# LeftSide.net
KiCad netlist of a schematic drawn in Altium Designer
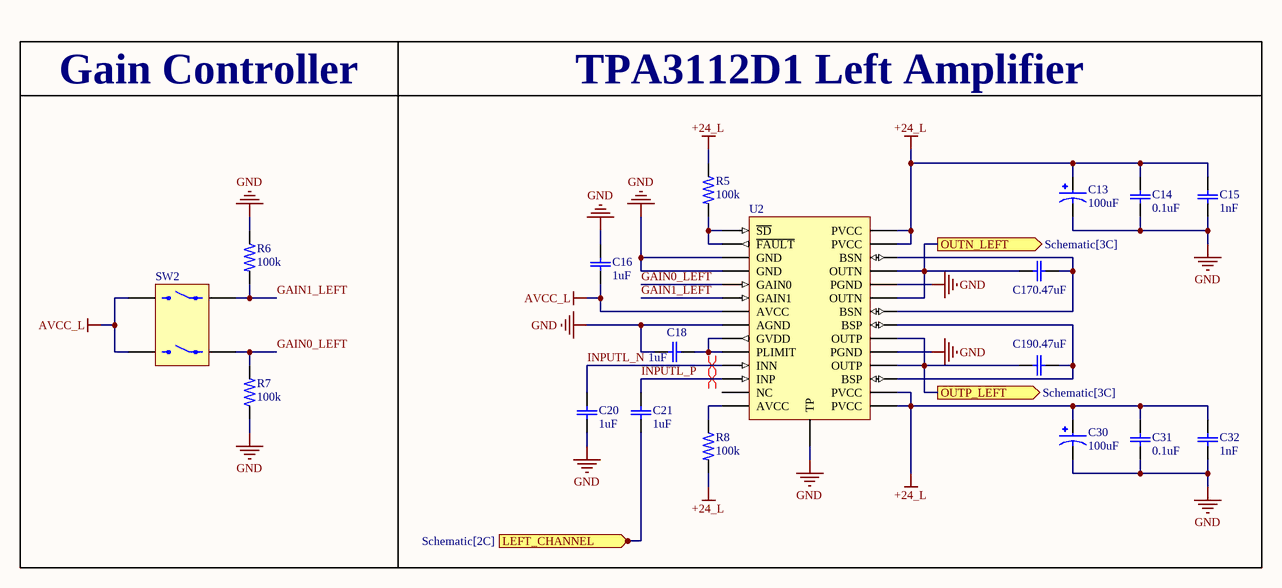
[diagram p0: LeftSide.SchDoc]

(export (version "E")
  (design (tool "Eeschema 10.0.6"))
  (components
    (comp (ref "C13")
      (value "100uF")
      (footprint "CAPRADIAL_16X10")
      (fields
        (field (name "DIGI-KEY_PART_NUMBER") "P13679-ND")
        (field (name "MP") "EEU-EE2W560")
        (field (name "MF") "Panasonic")
      )
      (libsource (lib "AltiumLibrary-Mugetsu") (part "CAP ELETRO/TANT"))
    )
    (comp (ref "C14")
      (value "0.1uF")
      (footprint "CERAMIC0805")
      (fields (field (name "MF") "KEMET") (field (name "MP") "TAJC226M025RNJ"))
      (libsource (lib "AltiumLibrary-Mugetsu") (part "Cap"))
    )
    (comp (ref "C15")
      (value "1nF")
      (footprint "CERAMIC0603")
      (fields (field (name "MF") "KEMET") (field (name "MP") "TAJC226M025RNJ"))
      (libsource (lib "AltiumLibrary-Mugetsu") (part "Cap"))
    )
    (comp (ref "C16")
      (value "1uF")
      (footprint "CERAMIC0603")
      (fields (field (name "MF") "KEMET") (field (name "MP") "TAJC226M025RNJ"))
      (libsource (lib "AltiumLibrary-Mugetsu") (part "Cap"))
    )
    (comp (ref "C17")
      (value "0.47uF")
      (footprint "CERAMIC0603")
      (fields (field (name "MF") "KEMET") (field (name "MP") "TAJC226M025RNJ"))
      (libsource (lib "AltiumLibrary-Mugetsu") (part "Cap"))
    )
    (comp (ref "C18")
      (value "1uF")
      (footprint "CERAMIC0603")
      (fields (field (name "MF") "KEMET") (field (name "MP") "TAJC226M025RNJ"))
      (libsource (lib "AltiumLibrary-Mugetsu") (part "Cap"))
    )
    (comp (ref "C19")
      (value "0.47uF")
      (footprint "CERAMIC0603")
      (fields (field (name "MF") "KEMET") (field (name "MP") "TAJC226M025RNJ"))
      (libsource (lib "AltiumLibrary-Mugetsu") (part "Cap"))
    )
    (comp (ref "C20")
      (value "1uF")
      (footprint "CERAMIC0603")
      (fields (field (name "MF") "KEMET") (field (name "MP") "TAJC226M025RNJ"))
      (libsource (lib "AltiumLibrary-Mugetsu") (part "Cap"))
    )
    (comp (ref "C21")
      (value "1uF")
      (footprint "CERAMIC0603")
      (fields (field (name "MF") "KEMET") (field (name "MP") "TAJC226M025RNJ"))
      (libsource (lib "AltiumLibrary-Mugetsu") (part "Cap"))
    )
    (comp (ref "C30")
      (value "100uF")
      (footprint "CAPRADIAL_16X10")
      (fields
        (field (name "DIGI-KEY_PART_NUMBER") "P13679-ND")
        (field (name "MP") "EEU-EE2W560")
        (field (name "MF") "Panasonic")
      )
      (libsource (lib "AltiumLibrary-Mugetsu") (part "CAP ELETRO/TANT"))
    )
    (comp (ref "C31")
      (value "0.1uF")
      (footprint "CERAMIC0805")
      (fields (field (name "MF") "KEMET") (field (name "MP") "TAJC226M025RNJ"))
      (libsource (lib "AltiumLibrary-Mugetsu") (part "Cap"))
    )
    (comp (ref "C32")
      (value "1nF")
      (footprint "CERAMIC0603")
      (fields (field (name "MF") "KEMET") (field (name "MP") "TAJC226M025RNJ"))
      (libsource (lib "AltiumLibrary-Mugetsu") (part "Cap"))
    )
    (comp (ref "R5")
      (value "100k")
      (footprint "RES0603")
      (fields (field (name "MP") "3-1879460-6"))
      (libsource (lib "AltiumLibrary-Mugetsu") (part "RESISTOR SMD"))
    )
    (comp (ref "R6")
      (value "100k")
      (footprint "RES0603")
      (fields (field (name "MP") "3-1879460-6"))
      (libsource (lib "AltiumLibrary-Mugetsu") (part "RESISTOR SMD"))
    )
    (comp (ref "R7")
      (value "100k")
      (footprint "RES0603")
      (fields (field (name "MP") "3-1879460-6"))
      (libsource (lib "AltiumLibrary-Mugetsu") (part "RESISTOR SMD"))
    )
    (comp (ref "R8")
      (value "100k")
      (footprint "RES0603")
      (fields (field (name "MP") "3-1879460-6"))
      (libsource (lib "AltiumLibrary-Mugetsu") (part "RESISTOR SMD"))
    )
    (comp (ref "SW2")
      (value "DIP SWITCH - 2 POS")
      (footprint "KF1001 - 2 POS")
      (libsource (lib "AltiumLibrary-Mugetsu") (part "DIP SWITCH - 2 POS"))
    )
    (comp (ref "U2")
      (value "TPA3112D1")
      (footprint "HTSSOP-28")
      (description "25W Filter-Free Mono Class-D Audio Power Amplifier")
      (libsource (lib "AltiumLibrary-Mugetsu") (part "TPA3112D1"))
    )
  )
  (nets
    (net (code "1") (name "+24_L") (class "Default")
      (node (ref "C13") (pin "P") (pinfunction "P_P") (pintype "passive"))
      (node (ref "C14") (pin "2") (pinfunction "C2_2") (pintype "passive"))
      (node (ref "C15") (pin "2") (pinfunction "C2_2") (pintype "passive"))
      (node (ref "C30") (pin "P") (pinfunction "P_P") (pintype "passive"))
      (node (ref "C31") (pin "2") (pinfunction "C2_2") (pintype "passive"))
      (node (ref "C32") (pin "2") (pinfunction "C2_2") (pintype "passive"))
      (node (ref "R5") (pin "1") (pinfunction "1_1") (pintype "passive"))
      (node (ref "R8") (pin "2") (pinfunction "2_2") (pintype "passive"))
      (node (ref "U2") (pin "15") (pinfunction "PVCC_15") (pintype "power_in"))
      (node (ref "U2") (pin "16") (pinfunction "PVCC_16") (pintype "power_in"))
      (node (ref "U2") (pin "27") (pinfunction "PVCC_27") (pintype "power_in"))
      (node (ref "U2") (pin "28") (pinfunction "PVCC_28") (pintype "power_in"))
    )
    (net (code "2") (name "/GAIN0_LEFT") (class "Default")
      (node (ref "R7") (pin "2") (pinfunction "2_2") (pintype "passive"))
      (node (ref "SW2") (pin "1") (pinfunction "1_1") (pintype "passive"))
      (node (ref "U2") (pin "5") (pinfunction "GAIN0_5") (pintype "input"))
    )
    (net (code "3") (name "/GAIN1_LEFT") (class "Default")
      (node (ref "R6") (pin "2") (pinfunction "2_2") (pintype "passive"))
      (node (ref "SW2") (pin "4") (pinfunction "4_4") (pintype "passive"))
      (node (ref "U2") (pin "6") (pinfunction "GAIN1_6") (pintype "input"))
    )
    (net (code "4") (name "/INPUTL_N") (class "Default")
      (node (ref "C20") (pin "2") (pinfunction "C2_2") (pintype "passive"))
      (node (ref "U2") (pin "11") (pinfunction "INN_11") (pintype "input"))
    )
    (net (code "5") (name "/INPUTL_P") (class "Default")
      (node (ref "C21") (pin "2") (pinfunction "C2_2") (pintype "passive"))
      (node (ref "U2") (pin "12") (pinfunction "INP_12") (pintype "input"))
    )
    (net (code "6") (name "/LEFT_CHANNEL") (class "Default")
      (node (ref "C21") (pin "1") (pinfunction "C1_1") (pintype "passive"))
    )
    (net (code "7") (name "/OUTN_LEFT") (class "Default")
      (node (ref "C17") (pin "2") (pinfunction "C2_2") (pintype "passive"))
      (node (ref "U2") (pin "23") (pinfunction "OUTN_23") (pintype "passive"))
      (node (ref "U2") (pin "25") (pinfunction "OUTN_25") (pintype "passive"))
    )
    (net (code "8") (name "/OUTP_LEFT") (class "Default")
      (node (ref "C19") (pin "2") (pinfunction "C2_2") (pintype "passive"))
      (node (ref "U2") (pin "18") (pinfunction "OUTP_18") (pintype "passive"))
      (node (ref "U2") (pin "20") (pinfunction "OUTP_20") (pintype "passive"))
    )
    (net (code "9") (name "AVCC_L") (class "Default")
      (node (ref "C16") (pin "2") (pinfunction "C2_2") (pintype "passive"))
      (node (ref "SW2") (pin "2") (pinfunction "2_2") (pintype "passive"))
      (node (ref "SW2") (pin "3") (pinfunction "3_3") (pintype "passive"))
      (node (ref "U2") (pin "7") (pinfunction "AVCC_7") (pintype "power_in"))
    )
    (net (code "10") (name "GND") (class "Default")
      (node (ref "C13") (pin "N") (pinfunction "N_N") (pintype "passive"))
      (node (ref "C14") (pin "1") (pinfunction "C1_1") (pintype "passive"))
      (node (ref "C15") (pin "1") (pinfunction "C1_1") (pintype "passive"))
      (node (ref "C16") (pin "1") (pinfunction "C1_1") (pintype "passive"))
      (node (ref "C18") (pin "2") (pinfunction "C2_2") (pintype "passive"))
      (node (ref "C20") (pin "1") (pinfunction "C1_1") (pintype "passive"))
      (node (ref "C30") (pin "N") (pinfunction "N_N") (pintype "passive"))
      (node (ref "C31") (pin "1") (pinfunction "C1_1") (pintype "passive"))
      (node (ref "C32") (pin "1") (pinfunction "C1_1") (pintype "passive"))
      (node (ref "R6") (pin "1") (pinfunction "1_1") (pintype "passive"))
      (node (ref "R7") (pin "1") (pinfunction "1_1") (pintype "passive"))
      (node (ref "U2") (pin "19") (pinfunction "PGND_19") (pintype "power_in"))
      (node (ref "U2") (pin "24") (pinfunction "PGND_24") (pintype "power_in"))
      (node (ref "U2") (pin "29") (pinfunction "TP_29") (pintype "power_in"))
      (node (ref "U2") (pin "3") (pinfunction "GND_3") (pintype "power_in"))
      (node (ref "U2") (pin "4") (pinfunction "GND_4") (pintype "power_in"))
      (node (ref "U2") (pin "8") (pinfunction "AGND_8") (pintype "power_in"))
    )
    (net (code "11") (name "Net-(C17-C1)") (class "Default")
      (node (ref "C17") (pin "1") (pinfunction "C1_1") (pintype "passive"))
      (node (ref "U2") (pin "22") (pinfunction "BSN_22") (pintype "bidirectional"))
      (node (ref "U2") (pin "26") (pinfunction "BSN_26") (pintype "bidirectional"))
    )
    (net (code "12") (name "Net-(C18-C1)") (class "Default")
      (node (ref "C18") (pin "1") (pinfunction "C1_1") (pintype "passive"))
      (node (ref "U2") (pin "10") (pinfunction "PLIMIT_10") (pintype "passive"))
      (node (ref "U2") (pin "9") (pinfunction "GVDD_9") (pintype "output"))
    )
    (net (code "13") (name "Net-(C19-C1)") (class "Default")
      (node (ref "C19") (pin "1") (pinfunction "C1_1") (pintype "passive"))
      (node (ref "U2") (pin "17") (pinfunction "BSP_17") (pintype "bidirectional"))
      (node (ref "U2") (pin "21") (pinfunction "BSP_21") (pintype "bidirectional"))
    )
    (net (code "14") (name "Net-(R8-Pad1)") (class "Default")
      (node (ref "R8") (pin "1") (pinfunction "1_1") (pintype "passive"))
      (node (ref "U2") (pin "14") (pinfunction "AVCC_14") (pintype "power_in"))
    )
    (net (code "15") (name "Net-(U2-~{FAULT})") (class "Default")
      (node (ref "R5") (pin "2") (pinfunction "2_2") (pintype "passive"))
      (node (ref "U2") (pin "1") (pinfunction "~{SD}_1") (pintype "input"))
      (node (ref "U2") (pin "2") (pinfunction "~{FAULT}_2") (pintype "output"))
    )
    (net (code "16") (name "unconnected-(U2-NC-Pad13)") (class "Default")
      (node (ref "U2") (pin "13") (pinfunction "NC_13") (pintype "passive"))
    )
  )
)
